# Schematics.net
KiCad netlist of a schematic drawn in EAGLE
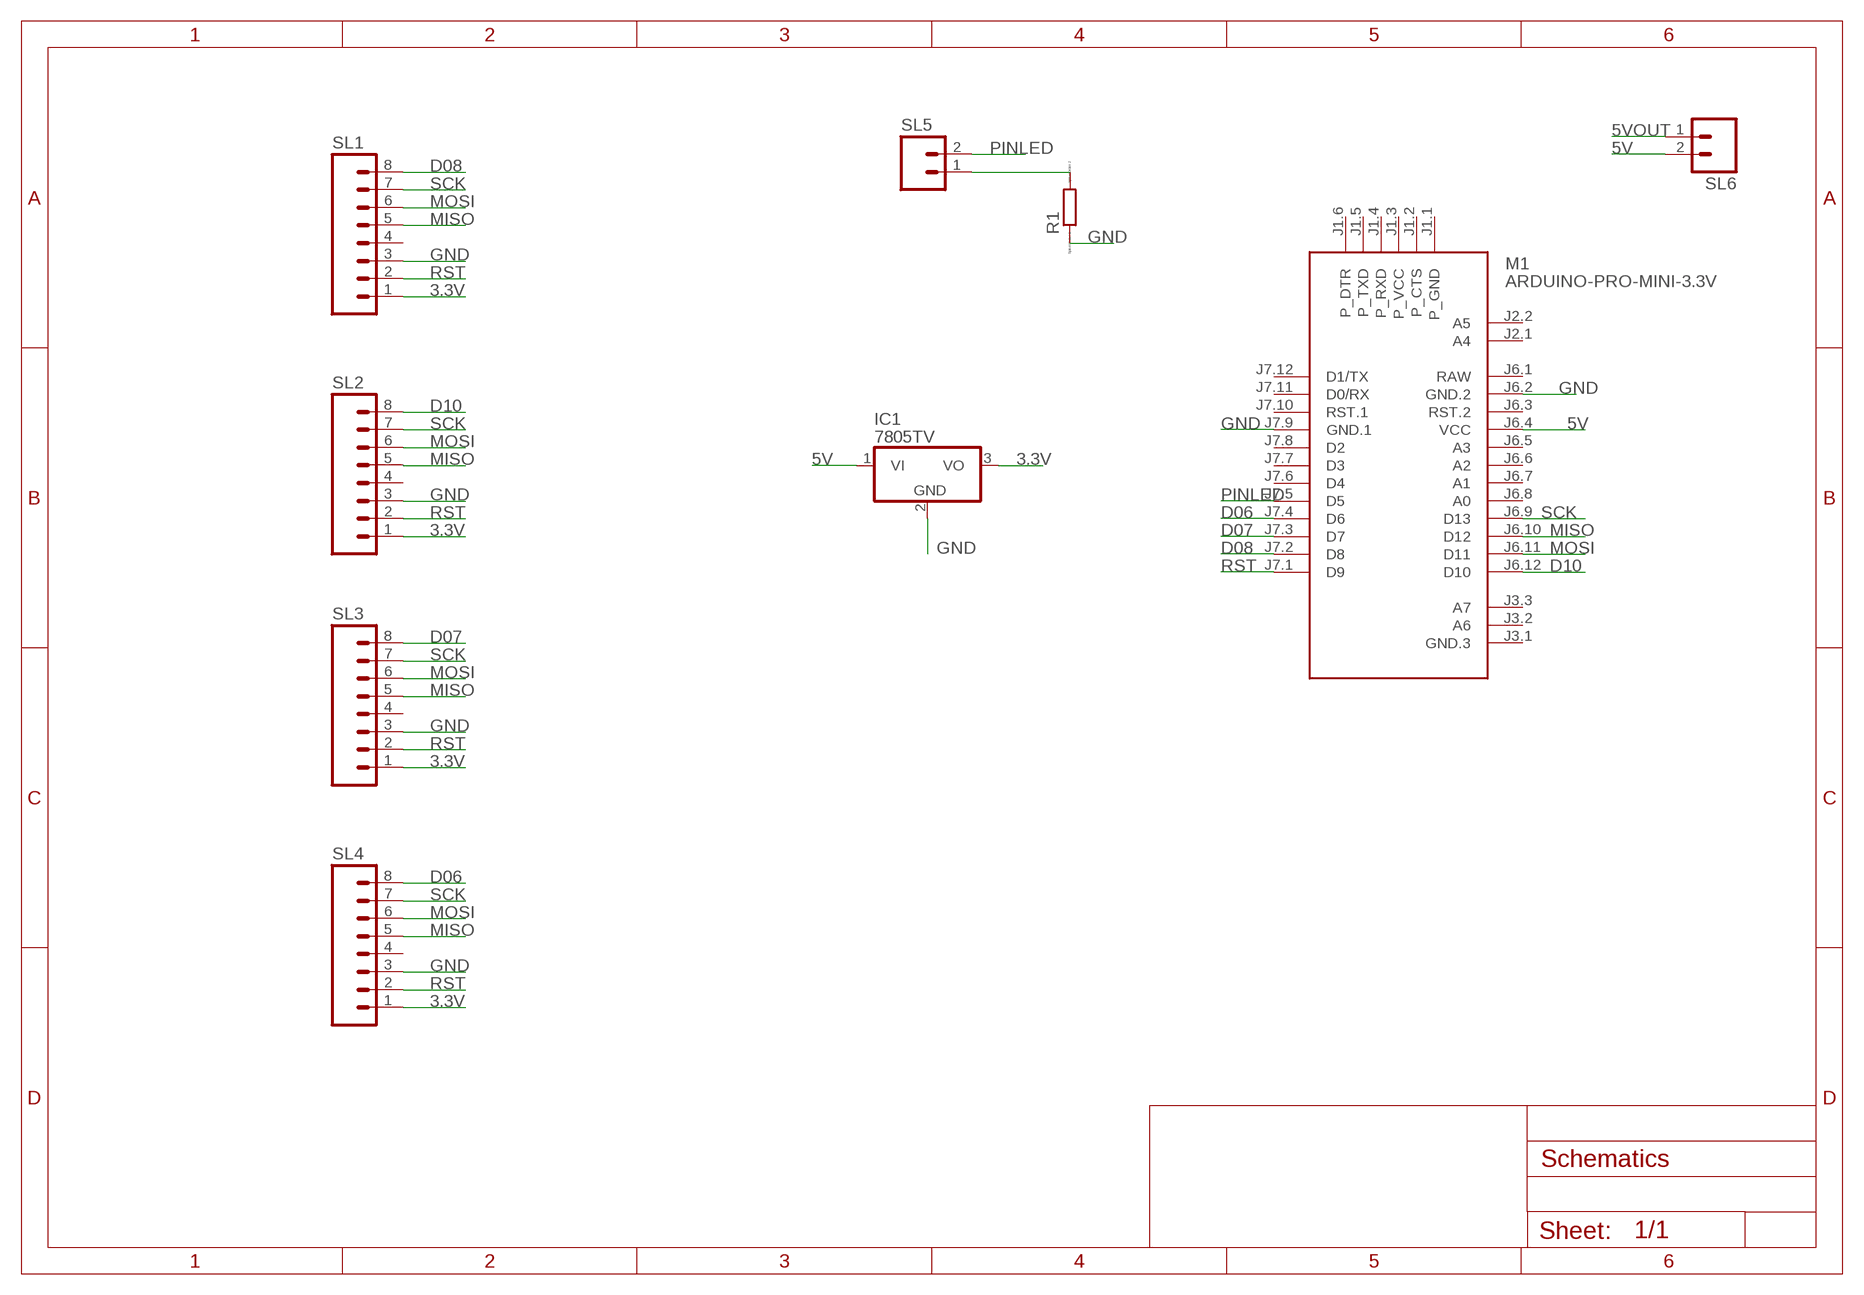
[diagram p0: schematic, sheet 1]

(export (version "E")
  (design (tool "Eeschema 10.0.6"))
  (components
    (comp (ref "IC1")
      (value "7805TV")
      (footprint "eagle-import:TO220V")
      (libsource (lib "eagle-import") (part "78TV05"))
    )
    (comp (ref "M1")
      (value "ARDUINO-PRO-MINI-3.3V")
      (footprint "eagle-import:ARDUINO-PRO-MINI")
      (libsource (lib "eagle-import") (part "ARDUINO-PRO-MINI-3.3V"))
    )
    (comp (ref "R1")
      (value "R0204/7")
      (footprint "eagle-import:0204_7")
      (libsource (lib "eagle-import") (part "R0204/7"))
    )
    (comp (ref "SL1")
      (value "M08")
      (footprint "eagle-import:08P")
      (libsource (lib "eagle-import") (part "M08"))
    )
    (comp (ref "SL2")
      (value "M08")
      (footprint "eagle-import:08P")
      (libsource (lib "eagle-import") (part "M08"))
    )
    (comp (ref "SL3")
      (value "M08")
      (footprint "eagle-import:08P")
      (libsource (lib "eagle-import") (part "M08"))
    )
    (comp (ref "SL4")
      (value "M08")
      (footprint "eagle-import:08P")
      (libsource (lib "eagle-import") (part "M08"))
    )
    (comp (ref "SL5")
      (value "M02")
      (footprint "eagle-import:02P")
      (libsource (lib "eagle-import") (part "M02"))
    )
    (comp (ref "SL6")
      (value "M02")
      (footprint "eagle-import:02P")
      (libsource (lib "eagle-import") (part "M02"))
    )
  )
  (nets
    (net (code "1") (name "/3.3V") (class "Default")
      (node (ref "IC1") (pin "3") (pinfunction "VO_3") (pintype "passive"))
      (node (ref "SL1") (pin "1") (pinfunction "1_1") (pintype "passive"))
      (node (ref "SL2") (pin "1") (pinfunction "1_1") (pintype "passive"))
      (node (ref "SL3") (pin "1") (pinfunction "1_1") (pintype "passive"))
      (node (ref "SL4") (pin "1") (pinfunction "1_1") (pintype "passive"))
    )
    (net (code "2") (name "/5V") (class "Default")
      (node (ref "IC1") (pin "1") (pinfunction "VI_1") (pintype "input"))
      (node (ref "M1") (pin "J6.4") (pinfunction "VCC_J6.4") (pintype "power_in"))
      (node (ref "SL6") (pin "2") (pinfunction "2_2") (pintype "passive"))
    )
    (net (code "3") (name "/5VOUT") (class "Default")
      (node (ref "SL6") (pin "1") (pinfunction "1_1") (pintype "passive"))
    )
    (net (code "4") (name "/D06") (class "Default")
      (node (ref "M1") (pin "J7.4") (pinfunction "D6_J7.4") (pintype "bidirectional"))
      (node (ref "SL4") (pin "8") (pinfunction "8_8") (pintype "passive"))
    )
    (net (code "5") (name "/D07") (class "Default")
      (node (ref "M1") (pin "J7.3") (pinfunction "D7_J7.3") (pintype "bidirectional"))
      (node (ref "SL3") (pin "8") (pinfunction "8_8") (pintype "passive"))
    )
    (net (code "6") (name "/D08") (class "Default")
      (node (ref "M1") (pin "J7.2") (pinfunction "D8_J7.2") (pintype "bidirectional"))
      (node (ref "SL1") (pin "8") (pinfunction "8_8") (pintype "passive"))
    )
    (net (code "7") (name "/D10") (class "Default")
      (node (ref "M1") (pin "J6.12") (pinfunction "D10_J6.12") (pintype "bidirectional"))
      (node (ref "SL2") (pin "8") (pinfunction "8_8") (pintype "passive"))
    )
    (net (code "8") (name "/GND") (class "Default")
      (node (ref "IC1") (pin "2") (pinfunction "GND_2") (pintype "passive"))
      (node (ref "M1") (pin "J6.2") (pinfunction "GND.2_J6.2") (pintype "power_in"))
      (node (ref "M1") (pin "J7.9") (pinfunction "GND.1_J7.9") (pintype "power_in"))
      (node (ref "R1") (pin "1") (pinfunction "1_1") (pintype "passive"))
      (node (ref "SL1") (pin "3") (pinfunction "3_3") (pintype "passive"))
      (node (ref "SL2") (pin "3") (pinfunction "3_3") (pintype "passive"))
      (node (ref "SL3") (pin "3") (pinfunction "3_3") (pintype "passive"))
      (node (ref "SL4") (pin "3") (pinfunction "3_3") (pintype "passive"))
    )
    (net (code "9") (name "/MISO") (class "Default")
      (node (ref "M1") (pin "J6.10") (pinfunction "D12_J6.10") (pintype "bidirectional"))
      (node (ref "SL1") (pin "5") (pinfunction "5_5") (pintype "passive"))
      (node (ref "SL2") (pin "5") (pinfunction "5_5") (pintype "passive"))
      (node (ref "SL3") (pin "5") (pinfunction "5_5") (pintype "passive"))
      (node (ref "SL4") (pin "5") (pinfunction "5_5") (pintype "passive"))
    )
    (net (code "10") (name "/MOSI") (class "Default")
      (node (ref "M1") (pin "J6.11") (pinfunction "D11_J6.11") (pintype "bidirectional"))
      (node (ref "SL1") (pin "6") (pinfunction "6_6") (pintype "passive"))
      (node (ref "SL2") (pin "6") (pinfunction "6_6") (pintype "passive"))
      (node (ref "SL3") (pin "6") (pinfunction "6_6") (pintype "passive"))
      (node (ref "SL4") (pin "6") (pinfunction "6_6") (pintype "passive"))
    )
    (net (code "11") (name "/PINLED") (class "Default")
      (node (ref "M1") (pin "J7.5") (pinfunction "D5_J7.5") (pintype "bidirectional"))
      (node (ref "SL5") (pin "2") (pinfunction "2_2") (pintype "passive"))
    )
    (net (code "12") (name "/RAW") (class "Default")
      (node (ref "M1") (pin "J6.1") (pinfunction "RAW_J6.1") (pintype "power_in"))
    )
    (net (code "13") (name "/RST") (class "Default")
      (node (ref "M1") (pin "J7.1") (pinfunction "D9_J7.1") (pintype "bidirectional"))
      (node (ref "SL1") (pin "2") (pinfunction "2_2") (pintype "passive"))
      (node (ref "SL2") (pin "2") (pinfunction "2_2") (pintype "passive"))
      (node (ref "SL3") (pin "2") (pinfunction "2_2") (pintype "passive"))
      (node (ref "SL4") (pin "2") (pinfunction "2_2") (pintype "passive"))
    )
    (net (code "14") (name "/SCK") (class "Default")
      (node (ref "M1") (pin "J6.9") (pinfunction "D13_J6.9") (pintype "bidirectional"))
      (node (ref "SL1") (pin "7") (pinfunction "7_7") (pintype "passive"))
      (node (ref "SL2") (pin "7") (pinfunction "7_7") (pintype "passive"))
      (node (ref "SL3") (pin "7") (pinfunction "7_7") (pintype "passive"))
      (node (ref "SL4") (pin "7") (pinfunction "7_7") (pintype "passive"))
    )
    (net (code "15") (name "Net-(R1-Pad2)") (class "Default")
      (node (ref "R1") (pin "2") (pinfunction "2_2") (pintype "passive"))
      (node (ref "SL5") (pin "1") (pinfunction "1_1") (pintype "passive"))
    )
    (net (code "16") (name "unconnected-(M1-A0-PadJ6.8)") (class "Default")
      (node (ref "M1") (pin "J6.8") (pinfunction "A0_J6.8") (pintype "bidirectional"))
    )
    (net (code "17") (name "unconnected-(M1-A1-PadJ6.7)") (class "Default")
      (node (ref "M1") (pin "J6.7") (pinfunction "A1_J6.7") (pintype "bidirectional"))
    )
    (net (code "18") (name "unconnected-(M1-A2-PadJ6.6)") (class "Default")
      (node (ref "M1") (pin "J6.6") (pinfunction "A2_J6.6") (pintype "bidirectional"))
    )
    (net (code "19") (name "unconnected-(M1-A3-PadJ6.5)") (class "Default")
      (node (ref "M1") (pin "J6.5") (pinfunction "A3_J6.5") (pintype "bidirectional"))
    )
    (net (code "20") (name "unconnected-(M1-A4-PadJ2.1)") (class "Default")
      (node (ref "M1") (pin "J2.1") (pinfunction "A4_J2.1") (pintype "bidirectional"))
    )
    (net (code "21") (name "unconnected-(M1-A5-PadJ2.2)") (class "Default")
      (node (ref "M1") (pin "J2.2") (pinfunction "A5_J2.2") (pintype "bidirectional"))
    )
    (net (code "22") (name "unconnected-(M1-A6-PadJ3.2)") (class "Default")
      (node (ref "M1") (pin "J3.2") (pinfunction "A6_J3.2") (pintype "bidirectional"))
    )
    (net (code "23") (name "unconnected-(M1-A7-PadJ3.3)") (class "Default")
      (node (ref "M1") (pin "J3.3") (pinfunction "A7_J3.3") (pintype "bidirectional"))
    )
    (net (code "24") (name "unconnected-(M1-D0{slash}RX-PadJ7.11)") (class "Default")
      (node (ref "M1") (pin "J7.11") (pinfunction "D0/RX_J7.11") (pintype "bidirectional"))
    )
    (net (code "25") (name "unconnected-(M1-D1{slash}TX-PadJ7.12)") (class "Default")
      (node (ref "M1") (pin "J7.12") (pinfunction "D1/TX_J7.12") (pintype "bidirectional"))
    )
    (net (code "26") (name "unconnected-(M1-D2-PadJ7.8)") (class "Default")
      (node (ref "M1") (pin "J7.8") (pinfunction "D2_J7.8") (pintype "bidirectional"))
    )
    (net (code "27") (name "unconnected-(M1-D3-PadJ7.7)") (class "Default")
      (node (ref "M1") (pin "J7.7") (pinfunction "D3_J7.7") (pintype "bidirectional"))
    )
    (net (code "28") (name "unconnected-(M1-D4-PadJ7.6)") (class "Default")
      (node (ref "M1") (pin "J7.6") (pinfunction "D4_J7.6") (pintype "bidirectional"))
    )
    (net (code "29") (name "unconnected-(M1-GND.3-PadJ3.1)") (class "Default")
      (node (ref "M1") (pin "J3.1") (pinfunction "GND.3_J3.1") (pintype "bidirectional"))
    )
    (net (code "30") (name "unconnected-(M1-P_CTS-PadJ1.2)") (class "Default")
      (node (ref "M1") (pin "J1.2") (pinfunction "P_CTS_J1.2") (pintype "bidirectional"))
    )
    (net (code "31") (name "unconnected-(M1-P_DTR-PadJ1.6)") (class "Default")
      (node (ref "M1") (pin "J1.6") (pinfunction "P_DTR_J1.6") (pintype "bidirectional"))
    )
    (net (code "32") (name "unconnected-(M1-P_GND-PadJ1.1)") (class "Default")
      (node (ref "M1") (pin "J1.1") (pinfunction "P_GND_J1.1") (pintype "bidirectional"))
    )
    (net (code "33") (name "unconnected-(M1-P_RXD-PadJ1.4)") (class "Default")
      (node (ref "M1") (pin "J1.4") (pinfunction "P_RXD_J1.4") (pintype "bidirectional"))
    )
    (net (code "34") (name "unconnected-(M1-P_TXD-PadJ1.5)") (class "Default")
      (node (ref "M1") (pin "J1.5") (pinfunction "P_TXD_J1.5") (pintype "bidirectional"))
    )
    (net (code "35") (name "unconnected-(M1-P_VCC-PadJ1.3)") (class "Default")
      (node (ref "M1") (pin "J1.3") (pinfunction "P_VCC_J1.3") (pintype "bidirectional"))
    )
    (net (code "36") (name "unconnected-(M1-RST.1-PadJ7.10)") (class "Default")
      (node (ref "M1") (pin "J7.10") (pinfunction "RST.1_J7.10") (pintype "bidirectional"))
    )
    (net (code "37") (name "unconnected-(M1-RST.2-PadJ6.3)") (class "Default")
      (node (ref "M1") (pin "J6.3") (pinfunction "RST.2_J6.3") (pintype "bidirectional"))
    )
    (net (code "38") (name "unconnected-(SL1-Pad4)") (class "Default")
      (node (ref "SL1") (pin "4") (pinfunction "4_4") (pintype "passive"))
    )
    (net (code "39") (name "unconnected-(SL2-Pad4)") (class "Default")
      (node (ref "SL2") (pin "4") (pinfunction "4_4") (pintype "passive"))
    )
    (net (code "40") (name "unconnected-(SL3-Pad4)") (class "Default")
      (node (ref "SL3") (pin "4") (pinfunction "4_4") (pintype "passive"))
    )
    (net (code "41") (name "unconnected-(SL4-Pad4)") (class "Default")
      (node (ref "SL4") (pin "4") (pinfunction "4_4") (pintype "passive"))
    )
  )
)
